# 11_RSSI2.net
KiCad netlist of a schematic drawn in Altium Designer
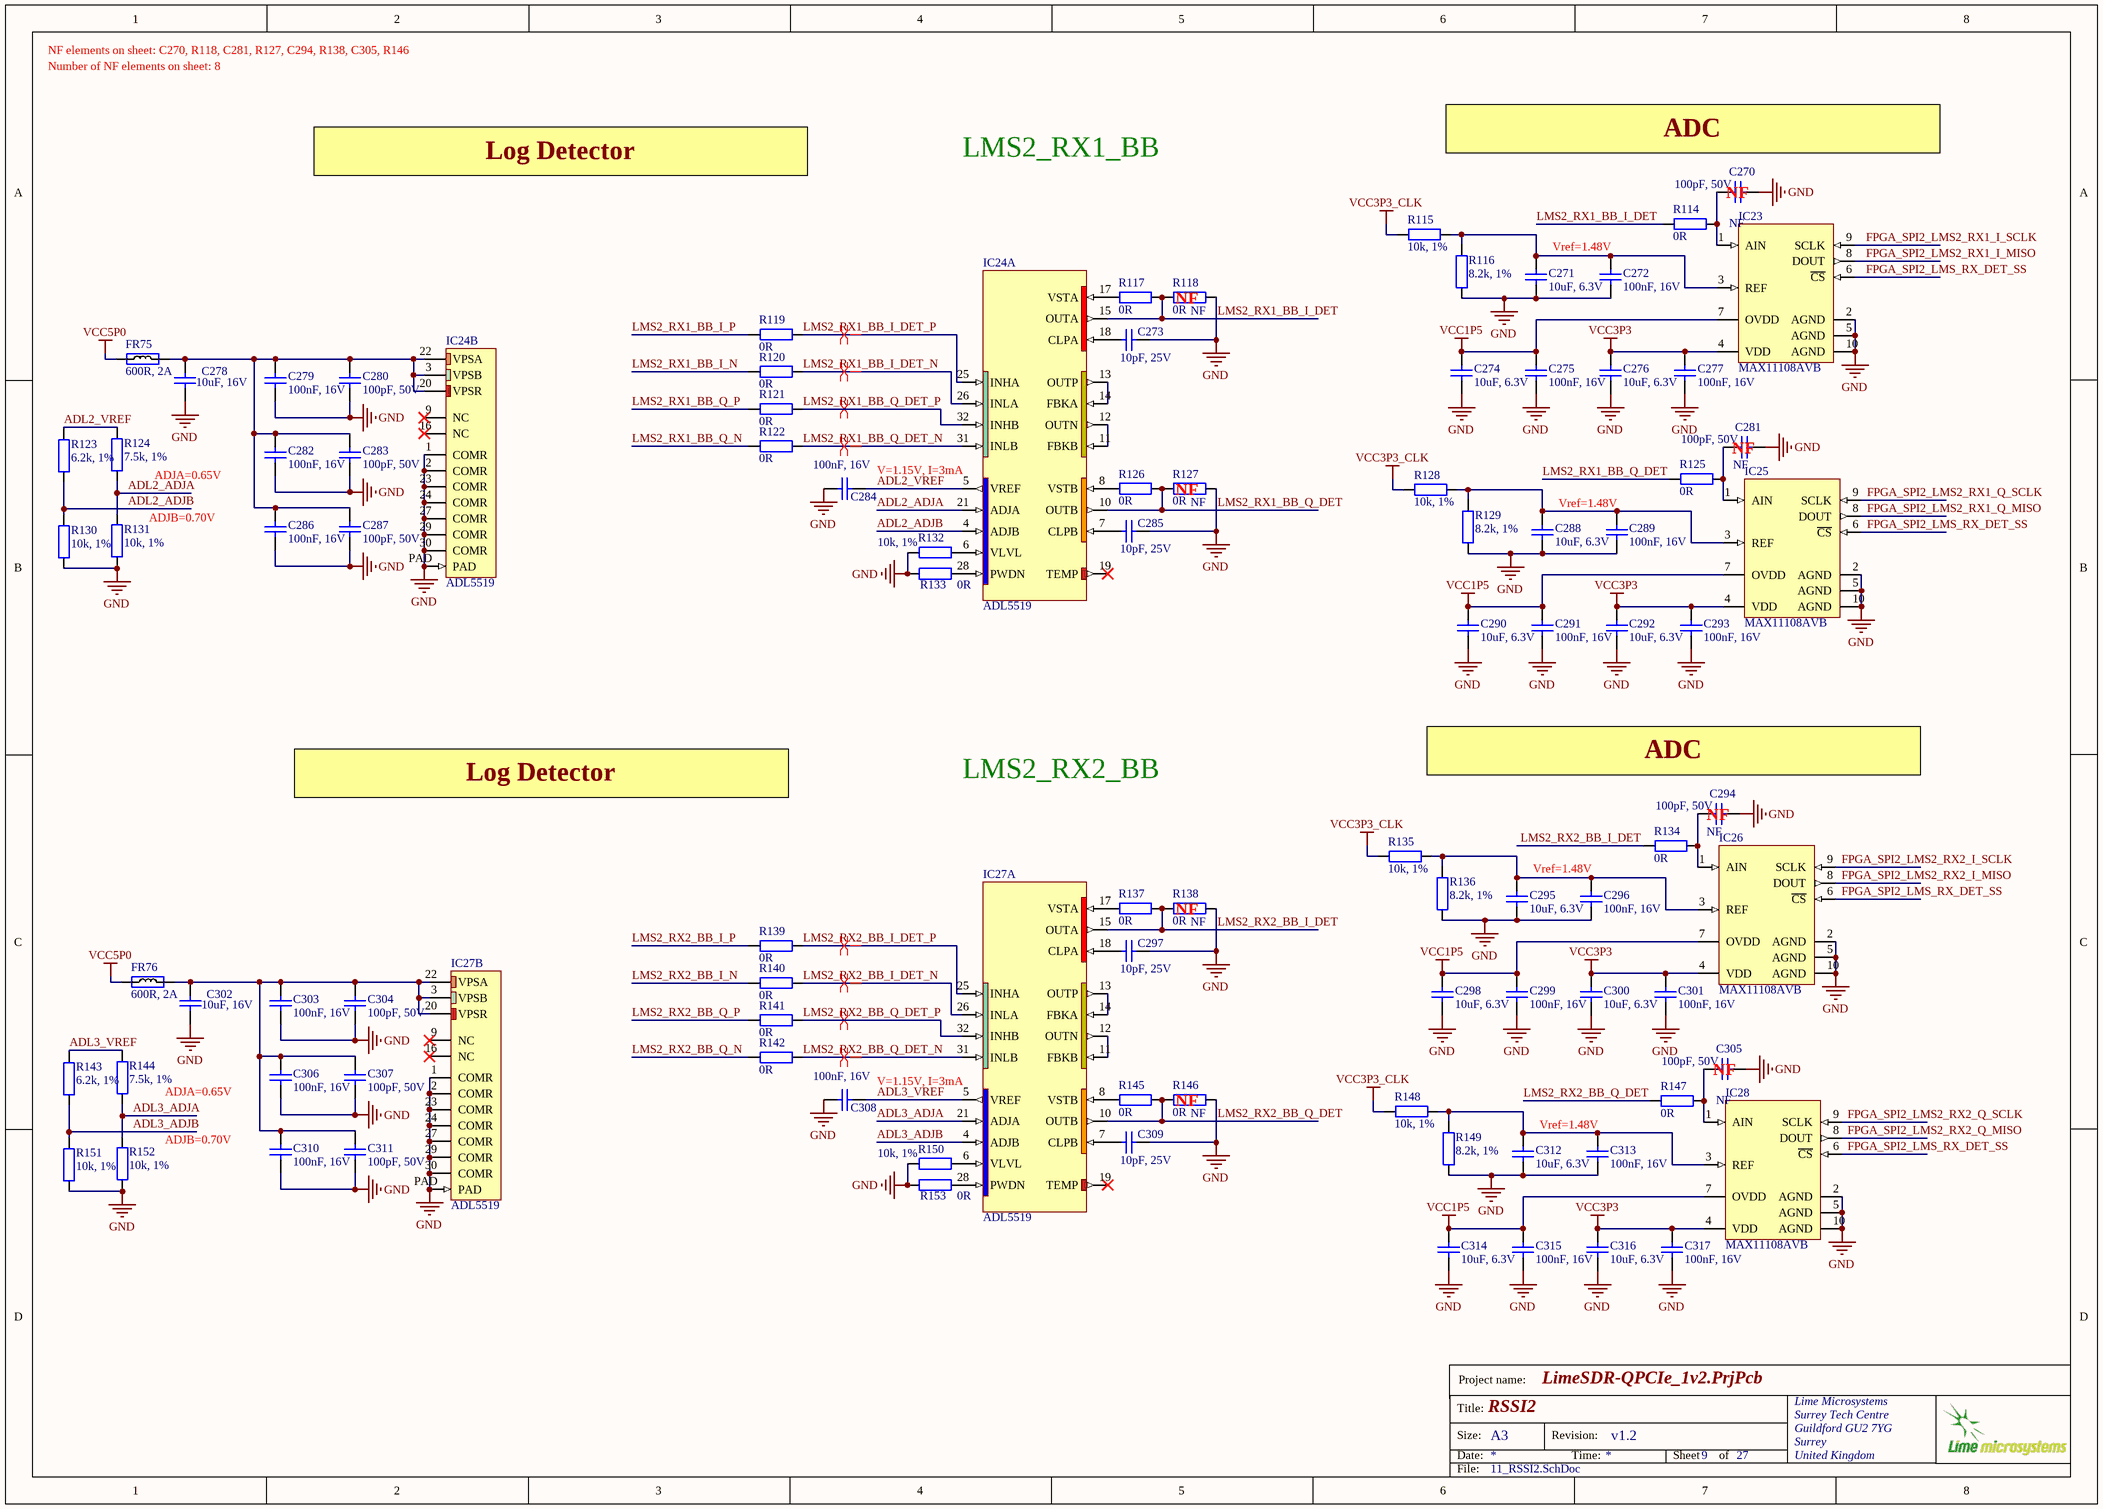
[diagram p0: 11_RSSI2.SchDoc]

(export (version "E")
  (design (tool "Eeschema 10.0.6"))
  (components
    (comp (ref "C270")
      (value "100pF, 50V")
      (footprint "CAP0402")
      (fields
        (field (name "ASSEMBLY INFO") "NF")
        (field (name "MANUFACTURER") "Yageo")
        (field (name "TOLERANCE") "±5%")
      )
      (libsource (lib "LimeMicroAltiumLib_schLib") (part "Cap_0402"))
    )
    (comp (ref "C271")
      (value "10uF, 6.3V")
      (footprint "CAP0603")
      (fields (field (name "TOLERANCE") "±20%") (field (name "MANUFACTURER") "Yageo"))
      (libsource (lib "LimeFPGAboard_schLib") (part "Cap_0603"))
    )
    (comp (ref "C272")
      (value "100nF, 16V")
      (footprint "CAP0402")
      (fields
        (field (name "MANUFACTURER") "Murata Electronics")
        (field (name "TOLERANCE") "10 %")
        (field (name "MANUFACTURER PART NUMBER") "GRM155R71C104KA88D")
      )
      (libsource (lib "LimeMicroAltiumLib_schLib") (part "Cap_0402"))
    )
    (comp (ref "C273")
      (value "10pF, 25V")
      (footprint "CAP0402")
      (fields (field (name "MANUFACTURER") "AVX"))
      (libsource (lib "LimeMicroAltiumLib_schLib") (part "Cap_0402"))
    )
    (comp (ref "C274")
      (value "10uF, 6.3V")
      (footprint "CAP0603")
      (fields (field (name "TOLERANCE") "±20%") (field (name "MANUFACTURER") "Yageo"))
      (libsource (lib "LimeFPGAboard_schLib") (part "Cap_0603"))
    )
    (comp (ref "C275")
      (value "100nF, 16V")
      (footprint "CAP0402")
      (fields
        (field (name "MANUFACTURER") "Murata Electronics")
        (field (name "TOLERANCE") "10 %")
        (field (name "MANUFACTURER PART NUMBER") "GRM155R71C104KA88D")
      )
      (libsource (lib "LimeMicroAltiumLib_schLib") (part "Cap_0402"))
    )
    (comp (ref "C276")
      (value "10uF, 6.3V")
      (footprint "CAP0603")
      (fields (field (name "TOLERANCE") "±20%") (field (name "MANUFACTURER") "Yageo"))
      (libsource (lib "LimeFPGAboard_schLib") (part "Cap_0603"))
    )
    (comp (ref "C277")
      (value "100nF, 16V")
      (footprint "CAP0402")
      (fields
        (field (name "MANUFACTURER") "Murata Electronics")
        (field (name "TOLERANCE") "10 %")
        (field (name "MANUFACTURER PART NUMBER") "GRM155R71C104KA88D")
      )
      (libsource (lib "LimeMicroAltiumLib_schLib") (part "Cap_0402"))
    )
    (comp (ref "C278")
      (value "10uF, 16V")
      (footprint "CAP0603")
      (fields (field (name "MANUFACTURER") "Yageo") (field (name "TOLERANCE") "±20%"))
      (libsource (lib "LimeMicroAltiumLib_schLib") (part "Cap_0603"))
    )
    (comp (ref "C279")
      (value "100nF, 16V")
      (footprint "CAP0402")
      (fields
        (field (name "MANUFACTURER") "Murata Electronics")
        (field (name "TOLERANCE") "10 %")
        (field (name "MANUFACTURER PART NUMBER") "GRM155R71C104KA88D")
      )
      (libsource (lib "LimeMicroAltiumLib_schLib") (part "Cap_0402"))
    )
    (comp (ref "C280")
      (value "100pF, 50V")
      (footprint "CAP0402")
      (fields (field (name "MANUFACTURER") "Yageo") (field (name "TOLERANCE") "±5%"))
      (libsource (lib "LimeMicroAltiumLib_schLib") (part "Cap_0402"))
    )
    (comp (ref "C281")
      (value "100pF, 50V")
      (footprint "CAP0402")
      (fields
        (field (name "ASSEMBLY INFO") "NF")
        (field (name "MANUFACTURER") "Yageo")
        (field (name "TOLERANCE") "±5%")
      )
      (libsource (lib "LimeMicroAltiumLib_schLib") (part "Cap_0402"))
    )
    (comp (ref "C282")
      (value "100nF, 16V")
      (footprint "CAP0402")
      (fields
        (field (name "MANUFACTURER") "Murata Electronics")
        (field (name "TOLERANCE") "10 %")
        (field (name "MANUFACTURER PART NUMBER") "GRM155R71C104KA88D")
      )
      (libsource (lib "LimeMicroAltiumLib_schLib") (part "Cap_0402"))
    )
    (comp (ref "C283")
      (value "100pF, 50V")
      (footprint "CAP0402")
      (fields (field (name "MANUFACTURER") "Yageo") (field (name "TOLERANCE") "±5%"))
      (libsource (lib "LimeMicroAltiumLib_schLib") (part "Cap_0402"))
    )
    (comp (ref "C284")
      (value "100nF, 16V")
      (footprint "CAP0402")
      (fields
        (field (name "MANUFACTURER") "Murata Electronics")
        (field (name "TOLERANCE") "10 %")
        (field (name "MANUFACTURER PART NUMBER") "GRM155R71C104KA88D")
      )
      (libsource (lib "LimeMicroAltiumLib_schLib") (part "Cap_0402"))
    )
    (comp (ref "C285")
      (value "10pF, 25V")
      (footprint "CAP0402")
      (fields (field (name "MANUFACTURER") "AVX"))
      (libsource (lib "LimeMicroAltiumLib_schLib") (part "Cap_0402"))
    )
    (comp (ref "C286")
      (value "100nF, 16V")
      (footprint "CAP0402")
      (fields
        (field (name "MANUFACTURER") "Murata Electronics")
        (field (name "TOLERANCE") "10 %")
        (field (name "MANUFACTURER PART NUMBER") "GRM155R71C104KA88D")
      )
      (libsource (lib "LimeMicroAltiumLib_schLib") (part "Cap_0402"))
    )
    (comp (ref "C287")
      (value "100pF, 50V")
      (footprint "CAP0402")
      (fields (field (name "MANUFACTURER") "Yageo") (field (name "TOLERANCE") "±5%"))
      (libsource (lib "LimeMicroAltiumLib_schLib") (part "Cap_0402"))
    )
    (comp (ref "C288")
      (value "10uF, 6.3V")
      (footprint "CAP0603")
      (fields (field (name "TOLERANCE") "±20%") (field (name "MANUFACTURER") "Yageo"))
      (libsource (lib "LimeFPGAboard_schLib") (part "Cap_0603"))
    )
    (comp (ref "C289")
      (value "100nF, 16V")
      (footprint "CAP0402")
      (fields
        (field (name "MANUFACTURER") "Murata Electronics")
        (field (name "TOLERANCE") "10 %")
        (field (name "MANUFACTURER PART NUMBER") "GRM155R71C104KA88D")
      )
      (libsource (lib "LimeMicroAltiumLib_schLib") (part "Cap_0402"))
    )
    (comp (ref "C290")
      (value "10uF, 6.3V")
      (footprint "CAP0603")
      (fields (field (name "TOLERANCE") "±20%") (field (name "MANUFACTURER") "Yageo"))
      (libsource (lib "LimeFPGAboard_schLib") (part "Cap_0603"))
    )
    (comp (ref "C291")
      (value "100nF, 16V")
      (footprint "CAP0402")
      (fields
        (field (name "MANUFACTURER") "Murata Electronics")
        (field (name "TOLERANCE") "10 %")
        (field (name "MANUFACTURER PART NUMBER") "GRM155R71C104KA88D")
      )
      (libsource (lib "LimeMicroAltiumLib_schLib") (part "Cap_0402"))
    )
    (comp (ref "C292")
      (value "10uF, 6.3V")
      (footprint "CAP0603")
      (fields (field (name "TOLERANCE") "±20%") (field (name "MANUFACTURER") "Yageo"))
      (libsource (lib "LimeFPGAboard_schLib") (part "Cap_0603"))
    )
    (comp (ref "C293")
      (value "100nF, 16V")
      (footprint "CAP0402")
      (fields
        (field (name "MANUFACTURER") "Murata Electronics")
        (field (name "TOLERANCE") "10 %")
        (field (name "MANUFACTURER PART NUMBER") "GRM155R71C104KA88D")
      )
      (libsource (lib "LimeMicroAltiumLib_schLib") (part "Cap_0402"))
    )
    (comp (ref "C294")
      (value "100pF, 50V")
      (footprint "CAP0402")
      (fields
        (field (name "ASSEMBLY INFO") "NF")
        (field (name "MANUFACTURER") "Yageo")
        (field (name "TOLERANCE") "±5%")
      )
      (libsource (lib "LimeMicroAltiumLib_schLib") (part "Cap_0402"))
    )
    (comp (ref "C295")
      (value "10uF, 6.3V")
      (footprint "CAP0603")
      (fields (field (name "TOLERANCE") "±20%") (field (name "MANUFACTURER") "Yageo"))
      (libsource (lib "LimeFPGAboard_schLib") (part "Cap_0603"))
    )
    (comp (ref "C296")
      (value "100nF, 16V")
      (footprint "CAP0402")
      (fields
        (field (name "MANUFACTURER") "Murata Electronics")
        (field (name "TOLERANCE") "10 %")
        (field (name "MANUFACTURER PART NUMBER") "GRM155R71C104KA88D")
      )
      (libsource (lib "LimeMicroAltiumLib_schLib") (part "Cap_0402"))
    )
    (comp (ref "C297")
      (value "10pF, 25V")
      (footprint "CAP0402")
      (fields (field (name "MANUFACTURER") "AVX"))
      (libsource (lib "LimeMicroAltiumLib_schLib") (part "Cap_0402"))
    )
    (comp (ref "C298")
      (value "10uF, 6.3V")
      (footprint "CAP0603")
      (fields (field (name "TOLERANCE") "±20%") (field (name "MANUFACTURER") "Yageo"))
      (libsource (lib "LimeFPGAboard_schLib") (part "Cap_0603"))
    )
    (comp (ref "C299")
      (value "100nF, 16V")
      (footprint "CAP0402")
      (fields
        (field (name "MANUFACTURER") "Murata Electronics")
        (field (name "TOLERANCE") "10 %")
        (field (name "MANUFACTURER PART NUMBER") "GRM155R71C104KA88D")
      )
      (libsource (lib "LimeMicroAltiumLib_schLib") (part "Cap_0402"))
    )
    (comp (ref "C300")
      (value "10uF, 6.3V")
      (footprint "CAP0603")
      (fields (field (name "TOLERANCE") "±20%") (field (name "MANUFACTURER") "Yageo"))
      (libsource (lib "LimeFPGAboard_schLib") (part "Cap_0603"))
    )
    (comp (ref "C301")
      (value "100nF, 16V")
      (footprint "CAP0402")
      (fields
        (field (name "MANUFACTURER") "Murata Electronics")
        (field (name "TOLERANCE") "10 %")
        (field (name "MANUFACTURER PART NUMBER") "GRM155R71C104KA88D")
      )
      (libsource (lib "LimeMicroAltiumLib_schLib") (part "Cap_0402"))
    )
    (comp (ref "C302")
      (value "10uF, 16V")
      (footprint "CAP0603")
      (fields (field (name "MANUFACTURER") "Yageo") (field (name "TOLERANCE") "±20%"))
      (libsource (lib "LimeMicroAltiumLib_schLib") (part "Cap_0603"))
    )
    (comp (ref "C303")
      (value "100nF, 16V")
      (footprint "CAP0402")
      (fields
        (field (name "MANUFACTURER") "Murata Electronics")
        (field (name "TOLERANCE") "10 %")
        (field (name "MANUFACTURER PART NUMBER") "GRM155R71C104KA88D")
      )
      (libsource (lib "LimeMicroAltiumLib_schLib") (part "Cap_0402"))
    )
    (comp (ref "C304")
      (value "100pF, 50V")
      (footprint "CAP0402")
      (fields (field (name "MANUFACTURER") "Yageo") (field (name "TOLERANCE") "±5%"))
      (libsource (lib "LimeMicroAltiumLib_schLib") (part "Cap_0402"))
    )
    (comp (ref "C305")
      (value "100pF, 50V")
      (footprint "CAP0402")
      (fields
        (field (name "ASSEMBLY INFO") "NF")
        (field (name "MANUFACTURER") "Yageo")
        (field (name "TOLERANCE") "±5%")
      )
      (libsource (lib "LimeMicroAltiumLib_schLib") (part "Cap_0402"))
    )
    (comp (ref "C306")
      (value "100nF, 16V")
      (footprint "CAP0402")
      (fields
        (field (name "MANUFACTURER") "Murata Electronics")
        (field (name "TOLERANCE") "10 %")
        (field (name "MANUFACTURER PART NUMBER") "GRM155R71C104KA88D")
      )
      (libsource (lib "LimeMicroAltiumLib_schLib") (part "Cap_0402"))
    )
    (comp (ref "C307")
      (value "100pF, 50V")
      (footprint "CAP0402")
      (fields (field (name "MANUFACTURER") "Yageo") (field (name "TOLERANCE") "±5%"))
      (libsource (lib "LimeMicroAltiumLib_schLib") (part "Cap_0402"))
    )
    (comp (ref "C308")
      (value "100nF, 16V")
      (footprint "CAP0402")
      (fields
        (field (name "MANUFACTURER") "Murata Electronics")
        (field (name "TOLERANCE") "10 %")
        (field (name "MANUFACTURER PART NUMBER") "GRM155R71C104KA88D")
      )
      (libsource (lib "LimeMicroAltiumLib_schLib") (part "Cap_0402"))
    )
    (comp (ref "C309")
      (value "10pF, 25V")
      (footprint "CAP0402")
      (fields (field (name "MANUFACTURER") "AVX"))
      (libsource (lib "LimeMicroAltiumLib_schLib") (part "Cap_0402"))
    )
    (comp (ref "C310")
      (value "100nF, 16V")
      (footprint "CAP0402")
      (fields
        (field (name "MANUFACTURER") "Murata Electronics")
        (field (name "TOLERANCE") "10 %")
        (field (name "MANUFACTURER PART NUMBER") "GRM155R71C104KA88D")
      )
      (libsource (lib "LimeMicroAltiumLib_schLib") (part "Cap_0402"))
    )
    (comp (ref "C311")
      (value "100pF, 50V")
      (footprint "CAP0402")
      (fields (field (name "MANUFACTURER") "Yageo") (field (name "TOLERANCE") "±5%"))
      (libsource (lib "LimeMicroAltiumLib_schLib") (part "Cap_0402"))
    )
    (comp (ref "C312")
      (value "10uF, 6.3V")
      (footprint "CAP0603")
      (fields (field (name "TOLERANCE") "±20%") (field (name "MANUFACTURER") "Yageo"))
      (libsource (lib "LimeFPGAboard_schLib") (part "Cap_0603"))
    )
    (comp (ref "C313")
      (value "100nF, 16V")
      (footprint "CAP0402")
      (fields
        (field (name "MANUFACTURER") "Murata Electronics")
        (field (name "TOLERANCE") "10 %")
        (field (name "MANUFACTURER PART NUMBER") "GRM155R71C104KA88D")
      )
      (libsource (lib "LimeMicroAltiumLib_schLib") (part "Cap_0402"))
    )
    (comp (ref "C314")
      (value "10uF, 6.3V")
      (footprint "CAP0603")
      (fields (field (name "TOLERANCE") "±20%") (field (name "MANUFACTURER") "Yageo"))
      (libsource (lib "LimeFPGAboard_schLib") (part "Cap_0603"))
    )
    (comp (ref "C315")
      (value "100nF, 16V")
      (footprint "CAP0402")
      (fields
        (field (name "MANUFACTURER") "Murata Electronics")
        (field (name "TOLERANCE") "10 %")
        (field (name "MANUFACTURER PART NUMBER") "GRM155R71C104KA88D")
      )
      (libsource (lib "LimeMicroAltiumLib_schLib") (part "Cap_0402"))
    )
    (comp (ref "C316")
      (value "10uF, 6.3V")
      (footprint "CAP0603")
      (fields (field (name "TOLERANCE") "±20%") (field (name "MANUFACTURER") "Yageo"))
      (libsource (lib "LimeFPGAboard_schLib") (part "Cap_0603"))
    )
    (comp (ref "C317")
      (value "100nF, 16V")
      (footprint "CAP0402")
      (fields
        (field (name "MANUFACTURER") "Murata Electronics")
        (field (name "TOLERANCE") "10 %")
        (field (name "MANUFACTURER PART NUMBER") "GRM155R71C104KA88D")
      )
      (libsource (lib "LimeMicroAltiumLib_schLib") (part "Cap_0402"))
    )
    (comp (ref "FR75")
      (value "600R, 2A")
      (footprint "RES0805")
      (fields (field (name "MANUFACTURER") "TDK"))
      (libsource (lib "LimeMicroAltiumLib_schLib") (part "Ferrite"))
    )
    (comp (ref "FR76")
      (value "600R, 2A")
      (footprint "RES0805")
      (fields (field (name "MANUFACTURER") "TDK"))
      (libsource (lib "LimeMicroAltiumLib_schLib") (part "Ferrite"))
    )
    (comp (ref "IC23")
      (value "MAX11108AVB")
      (footprint "MAX11108AVB+T")
      (fields (field (name "MANUFACTURER") "Maxim Integrated"))
      (libsource (lib "LimeMicroAltiumLib_schLib") (part "MAX11108AVB+T"))
    )
    (comp (ref "IC24")
      (value "ADL5519")
      (footprint "ADL5519_32LFCSP")
      (fields (field (name "MANUFACTURER") "Analog Devices Inc."))
      (libsource (lib "LimeMicroAltiumLib_schLib") (part "ADL5519"))
    )
    (comp (ref "IC25")
      (value "MAX11108AVB")
      (footprint "MAX11108AVB+T")
      (fields (field (name "MANUFACTURER") "Maxim Integrated"))
      (libsource (lib "LimeMicroAltiumLib_schLib") (part "MAX11108AVB+T"))
    )
    (comp (ref "IC26")
      (value "MAX11108AVB")
      (footprint "MAX11108AVB+T")
      (fields (field (name "MANUFACTURER") "Maxim Integrated"))
      (libsource (lib "LimeMicroAltiumLib_schLib") (part "MAX11108AVB+T"))
    )
    (comp (ref "IC27")
      (value "ADL5519")
      (footprint "ADL5519_32LFCSP")
      (fields (field (name "MANUFACTURER") "Analog Devices Inc."))
      (libsource (lib "LimeMicroAltiumLib_schLib") (part "ADL5519"))
    )
    (comp (ref "IC28")
      (value "MAX11108AVB")
      (footprint "MAX11108AVB+T")
      (fields (field (name "MANUFACTURER") "Maxim Integrated"))
      (libsource (lib "LimeMicroAltiumLib_schLib") (part "MAX11108AVB+T"))
    )
    (comp (ref "R114")
      (value "0R")
      (footprint "RES0402")
      (fields (field (name "MANUFACTURER") "Yageo") (field (name "TOLERANCE") "Jumper"))
      (libsource (lib "LimeMicroAltiumLib_schLib") (part "Res_0402"))
    )
    (comp (ref "R115")
      (value "10k, 1%")
      (footprint "RES0402")
      (fields (field (name "MANUFACTURER") "Yageo") (field (name "TOLERANCE") "±1%"))
      (libsource (lib "LimeMicroAltiumLib_schLib") (part "Res_0402"))
    )
    (comp (ref "R116")
      (value "8.2k, 1%")
      (footprint "RES0402")
      (fields (field (name "MANUFACTURER") "Yageo") (field (name "TOLERANCE") "±1%"))
      (libsource (lib "LimeMicroAltiumLib_schLib") (part "Res_0402"))
    )
    (comp (ref "R117")
      (value "0R")
      (footprint "RES0402")
      (fields (field (name "MANUFACTURER") "Yageo") (field (name "TOLERANCE") "Jumper"))
      (libsource (lib "LimeMicroAltiumLib_schLib") (part "Res_0402"))
    )
    (comp (ref "R118")
      (value "0R")
      (footprint "RES0402")
      (fields
        (field (name "ASSEMBLY INFO") "NF")
        (field (name "MANUFACTURER") "Yageo")
        (field (name "TOLERANCE") "Jumper")
      )
      (libsource (lib "LimeMicroAltiumLib_schLib") (part "Res_0402"))
    )
    (comp (ref "R119")
      (value "0R")
      (footprint "RES0402")
      (fields (field (name "MANUFACTURER") "Yageo") (field (name "TOLERANCE") "Jumper"))
      (libsource (lib "LimeMicroAltiumLib_schLib") (part "Res_0402"))
    )
    (comp (ref "R120")
      (value "0R")
      (footprint "RES0402")
      (fields (field (name "MANUFACTURER") "Yageo") (field (name "TOLERANCE") "Jumper"))
      (libsource (lib "LimeMicroAltiumLib_schLib") (part "Res_0402"))
    )
    (comp (ref "R121")
      (value "0R")
      (footprint "RES0402")
      (fields (field (name "MANUFACTURER") "Yageo") (field (name "TOLERANCE") "Jumper"))
      (libsource (lib "LimeMicroAltiumLib_schLib") (part "Res_0402"))
    )
    (comp (ref "R122")
      (value "0R")
      (footprint "RES0402")
      (fields (field (name "MANUFACTURER") "Yageo") (field (name "TOLERANCE") "Jumper"))
      (libsource (lib "LimeMicroAltiumLib_schLib") (part "Res_0402"))
    )
    (comp (ref "R123")
      (value "6.2k, 1%")
      (footprint "RES0402")
      (fields
        (field (name "MANUFACTURER") "Yageo")
        (field (name "MANUFACTURER PART NUMBER") "RC0402FR-076K2L")
        (field (name "TOLERANCE") "±1%")
      )
      (libsource (lib "LimeMicroAltiumLib_schLib") (part "Res_0402"))
    )
    (comp (ref "R124")
      (value "7.5k, 1%")
      (footprint "RES0402")
      (fields
        (field (name "TOLERANCE") "±1%")
        (field (name "MANUFACTURER PART NUMBER") "RC0402FR-077K5L")
        (field (name "MANUFACTURER") "Yageo")
      )
      (libsource (lib "LimeMicroAltiumLib_schLib") (part "Res_0402"))
    )
    (comp (ref "R125")
      (value "0R")
      (footprint "RES0402")
      (fields (field (name "MANUFACTURER") "Yageo") (field (name "TOLERANCE") "Jumper"))
      (libsource (lib "LimeMicroAltiumLib_schLib") (part "Res_0402"))
    )
    (comp (ref "R126")
      (value "0R")
      (footprint "RES0402")
      (fields (field (name "MANUFACTURER") "Yageo") (field (name "TOLERANCE") "Jumper"))
      (libsource (lib "LimeMicroAltiumLib_schLib") (part "Res_0402"))
    )
    (comp (ref "R127")
      (value "0R")
      (footprint "RES0402")
      (fields
        (field (name "ASSEMBLY INFO") "NF")
        (field (name "MANUFACTURER") "Yageo")
        (field (name "TOLERANCE") "Jumper")
      )
      (libsource (lib "LimeMicroAltiumLib_schLib") (part "Res_0402"))
    )
    (comp (ref "R128")
      (value "10k, 1%")
      (footprint "RES0402")
      (fields (field (name "MANUFACTURER") "Yageo") (field (name "TOLERANCE") "±1%"))
      (libsource (lib "LimeMicroAltiumLib_schLib") (part "Res_0402"))
    )
    (comp (ref "R129")
      (value "8.2k, 1%")
      (footprint "RES0402")
      (fields (field (name "MANUFACTURER") "Yageo") (field (name "TOLERANCE") "±1%"))
      (libsource (lib "LimeMicroAltiumLib_schLib") (part "Res_0402"))
    )
    (comp (ref "R130")
      (value "10k, 1%")
      (footprint "RES0402")
      (fields (field (name "MANUFACTURER") "Yageo") (field (name "TOLERANCE") "±1%"))
      (libsource (lib "LimeMicroAltiumLib_schLib") (part "Res_0402"))
    )
    (comp (ref "R131")
      (value "10k, 1%")
      (footprint "RES0402")
      (fields (field (name "MANUFACTURER") "Yageo") (field (name "TOLERANCE") "±1%"))
      (libsource (lib "LimeMicroAltiumLib_schLib") (part "Res_0402"))
    )
    (comp (ref "R132")
      (value "10k, 1%")
      (footprint "RES0402")
      (fields (field (name "MANUFACTURER") "Yageo") (field (name "TOLERANCE") "±1%"))
      (libsource (lib "LimeMicroAltiumLib_schLib") (part "Res_0402"))
    )
    (comp (ref "R133")
      (value "0R")
      (footprint "RES0402")
      (fields (field (name "MANUFACTURER") "Yageo") (field (name "TOLERANCE") "Jumper"))
      (libsource (lib "LimeMicroAltiumLib_schLib") (part "Res_0402"))
    )
    (comp (ref "R134")
      (value "0R")
      (footprint "RES0402")
      (fields (field (name "MANUFACTURER") "Yageo") (field (name "TOLERANCE") "Jumper"))
      (libsource (lib "LimeMicroAltiumLib_schLib") (part "Res_0402"))
    )
    (comp (ref "R135")
      (value "10k, 1%")
      (footprint "RES0402")
      (fields (field (name "MANUFACTURER") "Yageo") (field (name "TOLERANCE") "±1%"))
      (libsource (lib "LimeMicroAltiumLib_schLib") (part "Res_0402"))
    )
    (comp (ref "R136")
      (value "8.2k, 1%")
      (footprint "RES0402")
      (fields (field (name "MANUFACTURER") "Yageo") (field (name "TOLERANCE") "±1%"))
      (libsource (lib "LimeMicroAltiumLib_schLib") (part "Res_0402"))
    )
    (comp (ref "R137")
      (value "0R")
      (footprint "RES0402")
      (fields (field (name "MANUFACTURER") "Yageo") (field (name "TOLERANCE") "Jumper"))
      (libsource (lib "LimeMicroAltiumLib_schLib") (part "Res_0402"))
    )
    (comp (ref "R138")
      (value "0R")
      (footprint "RES0402")
      (fields
        (field (name "ASSEMBLY INFO") "NF")
        (field (name "MANUFACTURER") "Yageo")
        (field (name "TOLERANCE") "Jumper")
      )
      (libsource (lib "LimeMicroAltiumLib_schLib") (part "Res_0402"))
    )
    (comp (ref "R139")
      (value "0R")
      (footprint "RES0402")
      (fields (field (name "MANUFACTURER") "Yageo") (field (name "TOLERANCE") "Jumper"))
      (libsource (lib "LimeMicroAltiumLib_schLib") (part "Res_0402"))
    )
    (comp (ref "R140")
      (value "0R")
      (footprint "RES0402")
      (fields (field (name "MANUFACTURER") "Yageo") (field (name "TOLERANCE") "Jumper"))
      (libsource (lib "LimeMicroAltiumLib_schLib") (part "Res_0402"))
    )
    (comp (ref "R141")
      (value "0R")
      (footprint "RES0402")
      (fields (field (name "MANUFACTURER") "Yageo") (field (name "TOLERANCE") "Jumper"))
      (libsource (lib "LimeMicroAltiumLib_schLib") (part "Res_0402"))
    )
    (comp (ref "R142")
      (value "0R")
      (footprint "RES0402")
      (fields (field (name "MANUFACTURER") "Yageo") (field (name "TOLERANCE") "Jumper"))
      (libsource (lib "LimeMicroAltiumLib_schLib") (part "Res_0402"))
    )
    (comp (ref "R143")
      (value "6.2k, 1%")
      (footprint "RES0402")
      (fields
        (field (name "MANUFACTURER") "Yageo")
        (field (name "MANUFACTURER PART NUMBER") "RC0402FR-076K2L")
        (field (name "TOLERANCE") "±1%")
      )
      (libsource (lib "LimeMicroAltiumLib_schLib") (part "Res_0402"))
    )
    (comp (ref "R144")
      (value "7.5k, 1%")
      (footprint "RES0402")
      (fields
        (field (name "TOLERANCE") "±1%")
        (field (name "MANUFACTURER PART NUMBER") "RC0402FR-077K5L")
        (field (name "MANUFACTURER") "Yageo")
      )
      (libsource (lib "LimeMicroAltiumLib_schLib") (part "Res_0402"))
    )
    (comp (ref "R145")
      (value "0R")
      (footprint "RES0402")
      (fields (field (name "MANUFACTURER") "Yageo") (field (name "TOLERANCE") "Jumper"))
      (libsource (lib "LimeMicroAltiumLib_schLib") (part "Res_0402"))
    )
    (comp (ref "R146")
      (value "0R")
      (footprint "RES0402")
      (fields
        (field (name "ASSEMBLY INFO") "NF")
        (field (name "MANUFACTURER") "Yageo")
        (field (name "TOLERANCE") "Jumper")
      )
      (libsource (lib "LimeMicroAltiumLib_schLib") (part "Res_0402"))
    )
    (comp (ref "R147")
      (value "0R")
      (footprint "RES0402")
      (fields (field (name "MANUFACTURER") "Yageo") (field (name "TOLERANCE") "Jumper"))
      (libsource (lib "LimeMicroAltiumLib_schLib") (part "Res_0402"))
    )
    (comp (ref "R148")
      (value "10k, 1%")
      (footprint "RES0402")
      (fields (field (name "MANUFACTURER") "Yageo") (field (name "TOLERANCE") "±1%"))
      (libsource (lib "LimeMicroAltiumLib_schLib") (part "Res_0402"))
    )
    (comp (ref "R149")
      (value "8.2k, 1%")
      (footprint "RES0402")
      (fields (field (name "MANUFACTURER") "Yageo") (field (name "TOLERANCE") "±1%"))
      (libsource (lib "LimeMicroAltiumLib_schLib") (part "Res_0402"))
    )
    (comp (ref "R150")
      (value "10k, 1%")
      (footprint "RES0402")
      (fields (field (name "MANUFACTURER") "Yageo") (field (name "TOLERANCE") "±1%"))
      (libsource (lib "LimeMicroAltiumLib_schLib") (part "Res_0402"))
    )
    (comp (ref "R151")
      (value "10k, 1%")
      (footprint "RES0402")
      (fields (field (name "MANUFACTURER") "Yageo") (field (name "TOLERANCE") "±1%"))
      (libsource (lib "LimeMicroAltiumLib_schLib") (part "Res_0402"))
    )
    (comp (ref "R152")
      (value "10k, 1%")
      (footprint "RES0402")
      (fields (field (name "MANUFACTURER") "Yageo") (field (name "TOLERANCE") "±1%"))
      (libsource (lib "LimeMicroAltiumLib_schLib") (part "Res_0402"))
    )
    (comp (ref "R153")
      (value "0R")
      (footprint "RES0402")
      (fields (field (name "MANUFACTURER") "Yageo") (field (name "TOLERANCE") "Jumper"))
      (libsource (lib "LimeMicroAltiumLib_schLib") (part "Res_0402"))
    )
  )
  (nets
    (net (code "1") (name "/ADL2_ADJA") (class "Default")
      (node (ref "IC24") (pin "21") (pinfunction "ADJA_21") (pintype "input"))
      (node (ref "R124") (pin "1") (pinfunction "1_1") (pintype "passive"))
      (node (ref "R131") (pin "1") (pinfunction "1_1") (pintype "passive"))
    )
    (net (code "2") (name "/ADL2_ADJB") (class "Default")
      (node (ref "IC24") (pin "4") (pinfunction "ADJB_4") (pintype "input"))
      (node (ref "R123") (pin "1") (pinfunction "1_1") (pintype "passive"))
      (node (ref "R130") (pin "2") (pinfunction "2_2") (pintype "passive"))
    )
    (net (code "3") (name "/ADL2_VREF") (class "Default")
      (node (ref "C284") (pin "1") (pinfunction "1_1") (pintype "passive"))
      (node (ref "IC24") (pin "5") (pinfunction "VREF_5") (pintype "output"))
      (node (ref "R123") (pin "2") (pinfunction "2_2") (pintype "passive"))
      (node (ref "R124") (pin "2") (pinfunction "2_2") (pintype "passive"))
    )
    (net (code "4") (name "/ADL3_ADJA") (class "Default")
      (node (ref "IC27") (pin "21") (pinfunction "ADJA_21") (pintype "input"))
      (node (ref "R144") (pin "1") (pinfunction "1_1") (pintype "passive"))
      (node (ref "R152") (pin "1") (pinfunction "1_1") (pintype "passive"))
    )
    (net (code "5") (name "/ADL3_ADJB") (class "Default")
      (node (ref "IC27") (pin "4") (pinfunction "ADJB_4") (pintype "input"))
      (node (ref "R143") (pin "1") (pinfunction "1_1") (pintype "passive"))
      (node (ref "R151") (pin "2") (pinfunction "2_2") (pintype "passive"))
    )
    (net (code "6") (name "/ADL3_VREF") (class "Default")
      (node (ref "C308") (pin "1") (pinfunction "1_1") (pintype "passive"))
      (node (ref "IC27") (pin "5") (pinfunction "VREF_5") (pintype "output"))
      (node (ref "R143") (pin "2") (pinfunction "2_2") (pintype "passive"))
      (node (ref "R144") (pin "2") (pinfunction "2_2") (pintype "passive"))
    )
    (net (code "7") (name "/FPGA_SPI2_LMS2_RX1_I_MISO") (class "Default")
      (node (ref "IC23") (pin "8") (pinfunction "DOUT_8") (pintype "output"))
    )
    (net (code "8") (name "/FPGA_SPI2_LMS2_RX1_I_SCLK") (class "Default")
      (node (ref "IC23") (pin "9") (pinfunction "SCLK_9") (pintype "input"))
    )
    (net (code "9") (name "/FPGA_SPI2_LMS2_RX1_Q_MISO") (class "Default")
      (node (ref "IC25") (pin "8") (pinfunction "DOUT_8") (pintype "output"))
    )
    (net (code "10") (name "/FPGA_SPI2_LMS2_RX1_Q_SCLK") (class "Default")
      (node (ref "IC25") (pin "9") (pinfunction "SCLK_9") (pintype "input"))
    )
    (net (code "11") (name "/FPGA_SPI2_LMS2_RX2_I_MISO") (class "Default")
      (node (ref "IC26") (pin "8") (pinfunction "DOUT_8") (pintype "output"))
    )
    (net (code "12") (name "/FPGA_SPI2_LMS2_RX2_I_SCLK") (class "Default")
      (node (ref "IC26") (pin "9") (pinfunction "SCLK_9") (pintype "input"))
    )
    (net (code "13") (name "/FPGA_SPI2_LMS2_RX2_Q_MISO") (class "Default")
      (node (ref "IC28") (pin "8") (pinfunction "DOUT_8") (pintype "output"))
    )
    (net (code "14") (name "/FPGA_SPI2_LMS2_RX2_Q_SCLK") (class "Default")
      (node (ref "IC28") (pin "9") (pinfunction "SCLK_9") (pintype "input"))
    )
    (net (code "15") (name "/FPGA_SPI2_LMS_RX_DET_SS") (class "Default")
      (node (ref "IC23") (pin "6") (pinfunction "~{CS}_6") (pintype "input"))
      (node (ref "IC25") (pin "6") (pinfunction "~{CS}_6") (pintype "input"))
      (node (ref "IC26") (pin "6") (pinfunction "~{CS}_6") (pintype "input"))
      (node (ref "IC28") (pin "6") (pinfunction "~{CS}_6") (pintype "input"))
    )
    (net (code "16") (name "/LMS2_RX1_BB_I_DET") (class "Default")
      (node (ref "IC24") (pin "15") (pinfunction "OUTA_15") (pintype "output"))
      (node (ref "R114") (pin "2") (pinfunction "2_2") (pintype "passive"))
      (node (ref "R117") (pin "1") (pinfunction "1_1") (pintype "passive"))
      (node (ref "R118") (pin "2") (pinfunction "2_2") (pintype "passive"))
    )
    (net (code "17") (name "/LMS2_RX1_BB_I_DET_N") (class "Default")
      (node (ref "IC24") (pin "26") (pinfunction "INLA_26") (pintype "input"))
      (node (ref "R120") (pin "1") (pinfunction "1_1") (pintype "passive"))
    )
    (net (code "18") (name "/LMS2_RX1_BB_I_DET_P") (class "Default")
      (node (ref "IC24") (pin "25") (pinfunction "INHA_25") (pintype "input"))
      (node (ref "R119") (pin "1") (pinfunction "1_1") (pintype "passive"))
    )
    (net (code "19") (name "/LMS2_RX1_BB_I_N") (class "Default")
      (node (ref "R120") (pin "2") (pinfunction "2_2") (pintype "passive"))
    )
    (net (code "20") (name "/LMS2_RX1_BB_I_P") (class "Default")
      (node (ref "R119") (pin "2") (pinfunction "2_2") (pintype "passive"))
    )
    (net (code "21") (name "/LMS2_RX1_BB_Q_DET") (class "Default")
      (node (ref "IC24") (pin "10") (pinfunction "OUTB_10") (pintype "output"))
      (node (ref "R125") (pin "2") (pinfunction "2_2") (pintype "passive"))
      (node (ref "R126") (pin "1") (pinfunction "1_1") (pintype "passive"))
      (node (ref "R127") (pin "2") (pinfunction "2_2") (pintype "passive"))
    )
    (net (code "22") (name "/LMS2_RX1_BB_Q_DET_N") (class "Default")
      (node (ref "IC24") (pin "31") (pinfunction "INLB_31") (pintype "input"))
      (node (ref "R122") (pin "1") (pinfunction "1_1") (pintype "passive"))
    )
    (net (code "23") (name "/LMS2_RX1_BB_Q_DET_P") (class "Default")
      (node (ref "IC24") (pin "32") (pinfunction "INHB_32") (pintype "input"))
      (node (ref "R121") (pin "1") (pinfunction "1_1") (pintype "passive"))
    )
    (net (code "24") (name "/LMS2_RX1_BB_Q_N") (class "Default")
      (node (ref "R122") (pin "2") (pinfunction "2_2") (pintype "passive"))
    )
    (net (code "25") (name "/LMS2_RX1_BB_Q_P") (class "Default")
      (node (ref "R121") (pin "2") (pinfunction "2_2") (pintype "passive"))
    )
    (net (code "26") (name "/LMS2_RX2_BB_I_DET") (class "Default")
      (node (ref "IC27") (pin "15") (pinfunction "OUTA_15") (pintype "output"))
      (node (ref "R134") (pin "2") (pinfunction "2_2") (pintype "passive"))
      (node (ref "R137") (pin "1") (pinfunction "1_1") (pintype "passive"))
      (node (ref "R138") (pin "2") (pinfunction "2_2") (pintype "passive"))
    )
    (net (code "27") (name "/LMS2_RX2_BB_I_DET_N") (class "Default")
      (node (ref "IC27") (pin "26") (pinfunction "INLA_26") (pintype "input"))
      (node (ref "R140") (pin "1") (pinfunction "1_1") (pintype "passive"))
    )
    (net (code "28") (name "/LMS2_RX2_BB_I_DET_P") (class "Default")
      (node (ref "IC27") (pin "25") (pinfunction "INHA_25") (pintype "input"))
      (node (ref "R139") (pin "1") (pinfunction "1_1") (pintype "passive"))
    )
    (net (code "29") (name "/LMS2_RX2_BB_I_N") (class "Default")
      (node (ref "R140") (pin "2") (pinfunction "2_2") (pintype "passive"))
    )
    (net (code "30") (name "/LMS2_RX2_BB_I_P") (class "Default")
      (node (ref "R139") (pin "2") (pinfunction "2_2") (pintype "passive"))
    )
    (net (code "31") (name "/LMS2_RX2_BB_Q_DET") (class "Default")
      (node (ref "IC27") (pin "10") (pinfunction "OUTB_10") (pintype "output"))
      (node (ref "R145") (pin "1") (pinfunction "1_1") (pintype "passive"))
      (node (ref "R146") (pin "2") (pinfunction "2_2") (pintype "passive"))
      (node (ref "R147") (pin "2") (pinfunction "2_2") (pintype "passive"))
    )
    (net (code "32") (name "/LMS2_RX2_BB_Q_DET_N") (class "Default")
      (node (ref "IC27") (pin "31") (pinfunction "INLB_31") (pintype "input"))
      (node (ref "R142") (pin "1") (pinfunction "1_1") (pintype "passive"))
    )
    (net (code "33") (name "/LMS2_RX2_BB_Q_DET_P") (class "Default")
      (node (ref "IC27") (pin "32") (pinfunction "INHB_32") (pintype "input"))
      (node (ref "R141") (pin "1") (pinfunction "1_1") (pintype "passive"))
    )
    (net (code "34") (name "/LMS2_RX2_BB_Q_N") (class "Default")
      (node (ref "R142") (pin "2") (pinfunction "2_2") (pintype "passive"))
    )
    (net (code "35") (name "/LMS2_RX2_BB_Q_P") (class "Default")
      (node (ref "R141") (pin "2") (pinfunction "2_2") (pintype "passive"))
    )
    (net (code "36") (name "GND") (class "Default")
      (node (ref "C270") (pin "1") (pinfunction "1_1") (pintype "passive"))
      (node (ref "C271") (pin "1") (pinfunction "1_1") (pintype "passive"))
      (node (ref "C272") (pin "2") (pinfunction "2_2") (pintype "passive"))
      (node (ref "C273") (pin "2") (pinfunction "2_2") (pintype "passive"))
      (node (ref "C274") (pin "1") (pinfunction "1_1") (pintype "passive"))
      (node (ref "C275") (pin "2") (pinfunction "2_2") (pintype "passive"))
      (node (ref "C276") (pin "1") (pinfunction "1_1") (pintype "passive"))
      (node (ref "C277") (pin "2") (pinfunction "2_2") (pintype "passive"))
      (node (ref "C278") (pin "1") (pinfunction "1_1") (pintype "passive"))
      (node (ref "C279") (pin "1") (pinfunction "1_1") (pintype "passive"))
      (node (ref "C280") (pin "1") (pinfunction "1_1") (pintype "passive"))
      (node (ref "C281") (pin "1") (pinfunction "1_1") (pintype "passive"))
      (node (ref "C282") (pin "1") (pinfunction "1_1") (pintype "passive"))
      (node (ref "C283") (pin "1") (pinfunction "1_1") (pintype "passive"))
      (node (ref "C284") (pin "2") (pinfunction "2_2") (pintype "passive"))
      (node (ref "C285") (pin "2") (pinfunction "2_2") (pintype "passive"))
      (node (ref "C286") (pin "1") (pinfunction "1_1") (pintype "passive"))
      (node (ref "C287") (pin "1") (pinfunction "1_1") (pintype "passive"))
      (node (ref "C288") (pin "1") (pinfunction "1_1") (pintype "passive"))
      (node (ref "C289") (pin "2") (pinfunction "2_2") (pintype "passive"))
      (node (ref "C290") (pin "1") (pinfunction "1_1") (pintype "passive"))
      (node (ref "C291") (pin "2") (pinfunction "2_2") (pintype "passive"))
      (node (ref "C292") (pin "1") (pinfunction "1_1") (pintype "passive"))
      (node (ref "C293") (pin "2") (pinfunction "2_2") (pintype "passive"))
      (node (ref "C294") (pin "1") (pinfunction "1_1") (pintype "passive"))
      (node (ref "C295") (pin "1") (pinfunction "1_1") (pintype "passive"))
      (node (ref "C296") (pin "2") (pinfunction "2_2") (pintype "passive"))
      (node (ref "C297") (pin "2") (pinfunction "2_2") (pintype "passive"))
      (node (ref "C298") (pin "1") (pinfunction "1_1") (pintype "passive"))
      (node (ref "C299") (pin "2") (pinfunction "2_2") (pintype "passive"))
      (node (ref "C300") (pin "1") (pinfunction "1_1") (pintype "passive"))
      (node (ref "C301") (pin "2") (pinfunction "2_2") (pintype "passive"))
      (node (ref "C302") (pin "1") (pinfunction "1_1") (pintype "passive"))
      (node (ref "C303") (pin "1") (pinfunction "1_1") (pintype "passive"))
      (node (ref "C304") (pin "1") (pinfunction "1_1") (pintype "passive"))
      (node (ref "C305") (pin "1") (pinfunction "1_1") (pintype "passive"))
      (node (ref "C306") (pin "1") (pinfunction "1_1") (pintype "passive"))
      (node (ref "C307") (pin "1") (pinfunction "1_1") (pintype "passive"))
      (node (ref "C308") (pin "2") (pinfunction "2_2") (pintype "passive"))
      (node (ref "C309") (pin "2") (pinfunction "2_2") (pintype "passive"))
      (node (ref "C310") (pin "1") (pinfunction "1_1") (pintype "passive"))
      (node (ref "C311") (pin "1") (pinfunction "1_1") (pintype "passive"))
      (node (ref "C312") (pin "1") (pinfunction "1_1") (pintype "passive"))
      (node (ref "C313") (pin "2") (pinfunction "2_2") (pintype "passive"))
      (node (ref "C314") (pin "1") (pinfunction "1_1") (pintype "passive"))
      (node (ref "C315") (pin "2") (pinfunction "2_2") (pintype "passive"))
      (node (ref "C316") (pin "1") (pinfunction "1_1") (pintype "passive"))
      (node (ref "C317") (pin "2") (pinfunction "2_2") (pintype "passive"))
      (node (ref "IC23") (pin "10") (pinfunction "AGND_10") (pintype "passive"))
      (node (ref "IC23") (pin "2") (pinfunction "AGND_2") (pintype "passive"))
      (node (ref "IC23") (pin "5") (pinfunction "AGND_5") (pintype "passive"))
      (node (ref "IC24") (pin "1") (pinfunction "COMR_1") (pintype "passive"))
      (node (ref "IC24") (pin "2") (pinfunction "COMR_2") (pintype "passive"))
      (node (ref "IC24") (pin "23") (pinfunction "COMR_23") (pintype "passive"))
      (node (ref "IC24") (pin "24") (pinfunction "COMR_24") (pintype "passive"))
      (node (ref "IC24") (pin "27") (pinfunction "COMR_27") (pintype "passive"))
      (node (ref "IC24") (pin "29") (pinfunction "COMR_29") (pintype "passive"))
      (node (ref "IC24") (pin "30") (pinfunction "COMR_30") (pintype "passive"))
      (node (ref "IC24") (pin "PAD") (pinfunction "PAD_PAD") (pintype "input"))
      (node (ref "IC25") (pin "10") (pinfunction "AGND_10") (pintype "passive"))
      (node (ref "IC25") (pin "2") (pinfunction "AGND_2") (pintype "passive"))
      (node (ref "IC25") (pin "5") (pinfunction "AGND_5") (pintype "passive"))
      (node (ref "IC26") (pin "10") (pinfunction "AGND_10") (pintype "passive"))
      (node (ref "IC26") (pin "2") (pinfunction "AGND_2") (pintype "passive"))
      (node (ref "IC26") (pin "5") (pinfunction "AGND_5") (pintype "passive"))
      (node (ref "IC27") (pin "1") (pinfunction "COMR_1") (pintype "passive"))
      (node (ref "IC27") (pin "2") (pinfunction "COMR_2") (pintype "passive"))
      (node (ref "IC27") (pin "23") (pinfunction "COMR_23") (pintype "passive"))
      (node (ref "IC27") (pin "24") (pinfunction "COMR_24") (pintype "passive"))
      (node (ref "IC27") (pin "27") (pinfunction "COMR_27") (pintype "passive"))
      (node (ref "IC27") (pin "29") (pinfunction "COMR_29") (pintype "passive"))
      (node (ref "IC27") (pin "30") (pinfunction "COMR_30") (pintype "passive"))
      (node (ref "IC27") (pin "PAD") (pinfunction "PAD_PAD") (pintype "input"))
      (node (ref "IC28") (pin "10") (pinfunction "AGND_10") (pintype "passive"))
      (node (ref "IC28") (pin "2") (pinfunction "AGND_2") (pintype "passive"))
      (node (ref "IC28") (pin "5") (pinfunction "AGND_5") (pintype "passive"))
      (node (ref "R116") (pin "1") (pinfunction "1_1") (pintype "passive"))
      (node (ref "R118") (pin "1") (pinfunction "1_1") (pintype "passive"))
      (node (ref "R127") (pin "1") (pinfunction "1_1") (pintype "passive"))
      (node (ref "R129") (pin "1") (pinfunction "1_1") (pintype "passive"))
      (node (ref "R130") (pin "1") (pinfunction "1_1") (pintype "passive"))
      (node (ref "R131") (pin "2") (pinfunction "2_2") (pintype "passive"))
      (node (ref "R132") (pin "2") (pinfunction "2_2") (pintype "passive"))
      (node (ref "R133") (pin "2") (pinfunction "2_2") (pintype "passive"))
      (node (ref "R136") (pin "1") (pinfunction "1_1") (pintype "passive"))
      (node (ref "R138") (pin "1") (pinfunction "1_1") (pintype "passive"))
      (node (ref "R146") (pin "1") (pinfunction "1_1") (pintype "passive"))
      (node (ref "R149") (pin "1") (pinfunction "1_1") (pintype "passive"))
      (node (ref "R150") (pin "2") (pinfunction "2_2") (pintype "passive"))
      (node (ref "R151") (pin "1") (pinfunction "1_1") (pintype "passive"))
      (node (ref "R152") (pin "2") (pinfunction "2_2") (pintype "passive"))
      (node (ref "R153") (pin "2") (pinfunction "2_2") (pintype "passive"))
    )
    (net (code "37") (name "Net-(IC23-AIN)") (class "Default")
      (node (ref "C270") (pin "2") (pinfunction "2_2") (pintype "passive"))
      (node (ref "IC23") (pin "1") (pinfunction "AIN_1") (pintype "input"))
      (node (ref "R114") (pin "1") (pinfunction "1_1") (pintype "passive"))
    )
    (net (code "38") (name "Net-(IC23-REF)") (class "Default")
      (node (ref "C271") (pin "2") (pinfunction "2_2") (pintype "passive"))
      (node (ref "C272") (pin "1") (pinfunction "1_1") (pintype "passive"))
      (node (ref "IC23") (pin "3") (pinfunction "REF_3") (pintype "input"))
      (node (ref "R115") (pin "1") (pinfunction "1_1") (pintype "passive"))
      (node (ref "R116") (pin "2") (pinfunction "2_2") (pintype "passive"))
    )
    (net (code "39") (name "Net-(IC24A-CLPA)") (class "Default")
      (node (ref "C273") (pin "1") (pinfunction "1_1") (pintype "passive"))
      (node (ref "IC24") (pin "18") (pinfunction "CLPA_18") (pintype "input"))
    )
    (net (code "40") (name "Net-(IC24A-CLPB)") (class "Default")
      (node (ref "C285") (pin "1") (pinfunction "1_1") (pintype "passive"))
      (node (ref "IC24") (pin "7") (pinfunction "CLPB_7") (pintype "input"))
    )
    (net (code "41") (name "Net-(IC24A-FBKA)") (class "Default")
      (node (ref "IC24") (pin "13") (pinfunction "OUTP_13") (pintype "output"))
      (node (ref "IC24") (pin "14") (pinfunction "FBKA_14") (pintype "input"))
    )
    (net (code "42") (name "Net-(IC24A-FBKB)") (class "Default")
      (node (ref "IC24") (pin "11") (pinfunction "FBKB_11") (pintype "input"))
      (node (ref "IC24") (pin "12") (pinfunction "OUTN_12") (pintype "output"))
    )
    (net (code "43") (name "Net-(IC24A-PWDN)") (class "Default")
      (node (ref "IC24") (pin "28") (pinfunction "PWDN_28") (pintype "input"))
      (node (ref "R133") (pin "1") (pinfunction "1_1") (pintype "passive"))
    )
    (net (code "44") (name "Net-(IC24A-VLVL)") (class "Default")
      (node (ref "IC24") (pin "6") (pinfunction "VLVL_6") (pintype "input"))
      (node (ref "R132") (pin "1") (pinfunction "1_1") (pintype "passive"))
    )
    (net (code "45") (name "Net-(IC24A-VSTA)") (class "Default")
      (node (ref "IC24") (pin "17") (pinfunction "VSTA_17") (pintype "input"))
      (node (ref "R117") (pin "2") (pinfunction "2_2") (pintype "passive"))
    )
    (net (code "46") (name "Net-(IC24A-VSTB)") (class "Default")
      (node (ref "IC24") (pin "8") (pinfunction "VSTB_8") (pintype "input"))
      (node (ref "R126") (pin "2") (pinfunction "2_2") (pintype "passive"))
    )
    (net (code "47") (name "Net-(IC24B-VPSA)") (class "Default")
      (node (ref "C278") (pin "2") (pinfunction "2_2") (pintype "passive"))
      (node (ref "C279") (pin "2") (pinfunction "2_2") (pintype "passive"))
      (node (ref "C280") (pin "2") (pinfunction "2_2") (pintype "passive"))
      (node (ref "C282") (pin "2") (pinfunction "2_2") (pintype "passive"))
      (node (ref "C283") (pin "2") (pinfunction "2_2") (pintype "passive"))
      (node (ref "C286") (pin "2") (pinfunction "2_2") (pintype "passive"))
      (node (ref "C287") (pin "2") (pinfunction "2_2") (pintype "passive"))
      (node (ref "FR75") (pin "2") (pinfunction "2_2") (pintype "passive"))
      (node (ref "IC24") (pin "20") (pinfunction "VPSR_20") (pintype "power_in"))
      (node (ref "IC24") (pin "22") (pinfunction "VPSA_22") (pintype "power_in"))
      (node (ref "IC24") (pin "3") (pinfunction "VPSB_3") (pintype "power_in"))
    )
    (net (code "48") (name "Net-(IC25-AIN)") (class "Default")
      (node (ref "C281") (pin "2") (pinfunction "2_2") (pintype "passive"))
      (node (ref "IC25") (pin "1") (pinfunction "AIN_1") (pintype "input"))
      (node (ref "R125") (pin "1") (pinfunction "1_1") (pintype "passive"))
    )
    (net (code "49") (name "Net-(IC25-REF)") (class "Default")
      (node (ref "C288") (pin "2") (pinfunction "2_2") (pintype "passive"))
      (node (ref "C289") (pin "1") (pinfunction "1_1") (pintype "passive"))
      (node (ref "IC25") (pin "3") (pinfunction "REF_3") (pintype "input"))
      (node (ref "R128") (pin "1") (pinfunction "1_1") (pintype "passive"))
      (node (ref "R129") (pin "2") (pinfunction "2_2") (pintype "passive"))
    )
    (net (code "50") (name "Net-(IC26-AIN)") (class "Default")
      (node (ref "C294") (pin "2") (pinfunction "2_2") (pintype "passive"))
      (node (ref "IC26") (pin "1") (pinfunction "AIN_1") (pintype "input"))
      (node (ref "R134") (pin "1") (pinfunction "1_1") (pintype "passive"))
    )
    (net (code "51") (name "Net-(IC26-REF)") (class "Default")
      (node (ref "C295") (pin "2") (pinfunction "2_2") (pintype "passive"))
      (node (ref "C296") (pin "1") (pinfunction "1_1") (pintype "passive"))
      (node (ref "IC26") (pin "3") (pinfunction "REF_3") (pintype "input"))
      (node (ref "R135") (pin "1") (pinfunction "1_1") (pintype "passive"))
      (node (ref "R136") (pin "2") (pinfunction "2_2") (pintype "passive"))
    )
    (net (code "52") (name "Net-(IC27A-CLPA)") (class "Default")
      (node (ref "C297") (pin "1") (pinfunction "1_1") (pintype "passive"))
      (node (ref "IC27") (pin "18") (pinfunction "CLPA_18") (pintype "input"))
    )
    (net (code "53") (name "Net-(IC27A-CLPB)") (class "Default")
      (node (ref "C309") (pin "1") (pinfunction "1_1") (pintype "passive"))
      (node (ref "IC27") (pin "7") (pinfunction "CLPB_7") (pintype "input"))
    )
    (net (code "54") (name "Net-(IC27A-FBKA)") (class "Default")
      (node (ref "IC27") (pin "13") (pinfunction "OUTP_13") (pintype "output"))
      (node (ref "IC27") (pin "14") (pinfunction "FBKA_14") (pintype "input"))
    )
    (net (code "55") (name "Net-(IC27A-FBKB)") (class "Default")
      (node (ref "IC27") (pin "11") (pinfunction "FBKB_11") (pintype "input"))
      (node (ref "IC27") (pin "12") (pinfunction "OUTN_12") (pintype "output"))
    )
    (net (code "56") (name "Net-(IC27A-PWDN)") (class "Default")
      (node (ref "IC27") (pin "28") (pinfunction "PWDN_28") (pintype "input"))
      (node (ref "R153") (pin "1") (pinfunction "1_1") (pintype "passive"))
    )
    (net (code "57") (name "Net-(IC27A-VLVL)") (class "Default")
      (node (ref "IC27") (pin "6") (pinfunction "VLVL_6") (pintype "input"))
      (node (ref "R150") (pin "1") (pinfunction "1_1") (pintype "passive"))
    )
    (net (code "58") (name "Net-(IC27A-VSTA)") (class "Default")
      (node (ref "IC27") (pin "17") (pinfunction "VSTA_17") (pintype "input"))
      (node (ref "R137") (pin "2") (pinfunction "2_2") (pintype "passive"))
    )
    (net (code "59") (name "Net-(IC27A-VSTB)") (class "Default")
      (node (ref "IC27") (pin "8") (pinfunction "VSTB_8") (pintype "input"))
      (node (ref "R145") (pin "2") (pinfunction "2_2") (pintype "passive"))
    )
    (net (code "60") (name "Net-(IC27B-VPSA)") (class "Default")
      (node (ref "C302") (pin "2") (pinfunction "2_2") (pintype "passive"))
      (node (ref "C303") (pin "2") (pinfunction "2_2") (pintype "passive"))
      (node (ref "C304") (pin "2") (pinfunction "2_2") (pintype "passive"))
      (node (ref "C306") (pin "2") (pinfunction "2_2") (pintype "passive"))
      (node (ref "C307") (pin "2") (pinfunction "2_2") (pintype "passive"))
      (node (ref "C310") (pin "2") (pinfunction "2_2") (pintype "passive"))
      (node (ref "C311") (pin "2") (pinfunction "2_2") (pintype "passive"))
      (node (ref "FR76") (pin "2") (pinfunction "2_2") (pintype "passive"))
      (node (ref "IC27") (pin "20") (pinfunction "VPSR_20") (pintype "power_in"))
      (node (ref "IC27") (pin "22") (pinfunction "VPSA_22") (pintype "power_in"))
      (node (ref "IC27") (pin "3") (pinfunction "VPSB_3") (pintype "power_in"))
    )
    (net (code "61") (name "Net-(IC28-AIN)") (class "Default")
      (node (ref "C305") (pin "2") (pinfunction "2_2") (pintype "passive"))
      (node (ref "IC28") (pin "1") (pinfunction "AIN_1") (pintype "input"))
      (node (ref "R147") (pin "1") (pinfunction "1_1") (pintype "passive"))
    )
    (net (code "62") (name "Net-(IC28-REF)") (class "Default")
      (node (ref "C312") (pin "2") (pinfunction "2_2") (pintype "passive"))
      (node (ref "C313") (pin "1") (pinfunction "1_1") (pintype "passive"))
      (node (ref "IC28") (pin "3") (pinfunction "REF_3") (pintype "input"))
      (node (ref "R148") (pin "1") (pinfunction "1_1") (pintype "passive"))
      (node (ref "R149") (pin "2") (pinfunction "2_2") (pintype "passive"))
    )
    (net (code "63") (name "VCC1P5") (class "Default")
      (node (ref "C274") (pin "2") (pinfunction "2_2") (pintype "passive"))
      (node (ref "C275") (pin "1") (pinfunction "1_1") (pintype "passive"))
      (node (ref "C290") (pin "2") (pinfunction "2_2") (pintype "passive"))
      (node (ref "C291") (pin "1") (pinfunction "1_1") (pintype "passive"))
      (node (ref "C298") (pin "2") (pinfunction "2_2") (pintype "passive"))
      (node (ref "C299") (pin "1") (pinfunction "1_1") (pintype "passive"))
      (node (ref "C314") (pin "2") (pinfunction "2_2") (pintype "passive"))
      (node (ref "C315") (pin "1") (pinfunction "1_1") (pintype "passive"))
      (node (ref "IC23") (pin "7") (pinfunction "OVDD_7") (pintype "power_in"))
      (node (ref "IC25") (pin "7") (pinfunction "OVDD_7") (pintype "power_in"))
      (node (ref "IC26") (pin "7") (pinfunction "OVDD_7") (pintype "power_in"))
      (node (ref "IC28") (pin "7") (pinfunction "OVDD_7") (pintype "power_in"))
    )
    (net (code "64") (name "VCC3P3") (class "Default")
      (node (ref "C276") (pin "2") (pinfunction "2_2") (pintype "passive"))
      (node (ref "C277") (pin "1") (pinfunction "1_1") (pintype "passive"))
      (node (ref "C292") (pin "2") (pinfunction "2_2") (pintype "passive"))
      (node (ref "C293") (pin "1") (pinfunction "1_1") (pintype "passive"))
      (node (ref "C300") (pin "2") (pinfunction "2_2") (pintype "passive"))
      (node (ref "C301") (pin "1") (pinfunction "1_1") (pintype "passive"))
      (node (ref "C316") (pin "2") (pinfunction "2_2") (pintype "passive"))
      (node (ref "C317") (pin "1") (pinfunction "1_1") (pintype "passive"))
      (node (ref "IC23") (pin "4") (pinfunction "VDD_4") (pintype "power_in"))
      (node (ref "IC25") (pin "4") (pinfunction "VDD_4") (pintype "power_in"))
      (node (ref "IC26") (pin "4") (pinfunction "VDD_4") (pintype "power_in"))
      (node (ref "IC28") (pin "4") (pinfunction "VDD_4") (pintype "power_in"))
    )
    (net (code "65") (name "VCC3P3_CLK") (class "Default")
      (node (ref "R115") (pin "2") (pinfunction "2_2") (pintype "passive"))
      (node (ref "R128") (pin "2") (pinfunction "2_2") (pintype "passive"))
      (node (ref "R135") (pin "2") (pinfunction "2_2") (pintype "passive"))
      (node (ref "R148") (pin "2") (pinfunction "2_2") (pintype "passive"))
    )
    (net (code "66") (name "VCC5P0") (class "Default")
      (node (ref "FR75") (pin "1") (pinfunction "1_1") (pintype "passive"))
      (node (ref "FR76") (pin "1") (pinfunction "1_1") (pintype "passive"))
    )
    (net (code "67") (name "unconnected-(IC24A-TEMP-Pad19)") (class "Default")
      (node (ref "IC24") (pin "19") (pinfunction "TEMP_19") (pintype "output+no_connect"))
    )
    (net (code "68") (name "unconnected-(IC24B-NC-Pad9)") (class "Default")
      (node (ref "IC24") (pin "9") (pinfunction "NC_9") (pintype "passive+no_connect"))
    )
    (net (code "69") (name "unconnected-(IC24B-NC-Pad16)") (class "Default")
      (node (ref "IC24") (pin "16") (pinfunction "NC_16") (pintype "passive+no_connect"))
    )
    (net (code "70") (name "unconnected-(IC27A-TEMP-Pad19)") (class "Default")
      (node (ref "IC27") (pin "19") (pinfunction "TEMP_19") (pintype "output+no_connect"))
    )
    (net (code "71") (name "unconnected-(IC27B-NC-Pad9)") (class "Default")
      (node (ref "IC27") (pin "9") (pinfunction "NC_9") (pintype "passive+no_connect"))
    )
    (net (code "72") (name "unconnected-(IC27B-NC-Pad16)") (class "Default")
      (node (ref "IC27") (pin "16") (pinfunction "NC_16") (pintype "passive+no_connect"))
    )
  )
)
